# LED_Bar.net
KiCad netlist of a schematic drawn in EAGLE
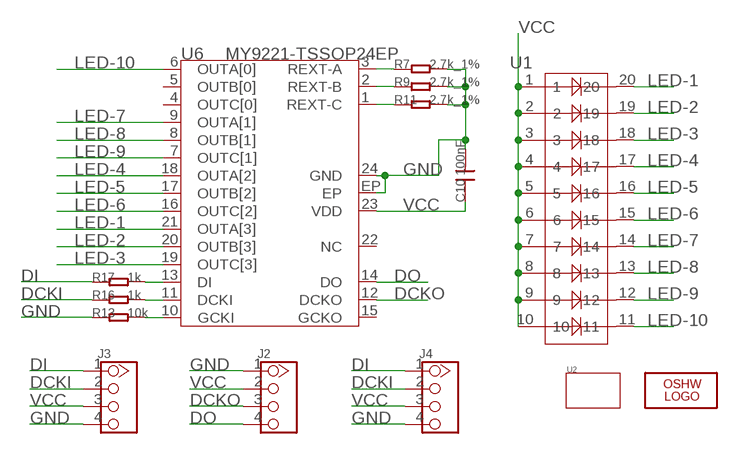
[diagram p0: schematic, sheet 1]

(export (version "E")
  (design (tool "Eeschema 10.0.6"))
  (components
    (comp (ref "C10")
      (value "100nF")
      (footprint "eagle-import:0603")
      (libsource (lib "eagle-import") (part "C-0603"))
    )
    (comp (ref "J2")
      (value "HEADER-4P-90D")
      (footprint "eagle-import:4P-2.54-90")
      (libsource (lib "eagle-import") (part "HEADER-4P-90D"))
    )
    (comp (ref "J3")
      (value "HEADER-4P'2.54-90D-FEMALE'")
      (footprint "eagle-import:4P-2.54-90D-FEMALE")
      (libsource (lib "eagle-import") (part "HEADER-4P'2.54-90D-FEMALE'"))
    )
    (comp (ref "J4")
      (value "TWIG-4P-2.0-2.0")
      (footprint "eagle-import:4P-2.0")
      (libsource (lib "eagle-import") (part "TWIG-4P-2.0-2.0"))
    )
    (comp (ref "LOGO1")
      (value "LOGO-OSHW-FILLX0150-NT")
      (footprint "eagle-import:OSHW_FILLX150_NOTEXT")
      (libsource (lib "eagle-import") (part "LOGO-OSHW-FILLX0150-NT"))
    )
    (comp (ref "R7")
      (value "2.7k_1%")
      (footprint "eagle-import:0603")
      (libsource (lib "eagle-import") (part "R-0603"))
    )
    (comp (ref "R9")
      (value "2.7k_1%")
      (footprint "eagle-import:0603")
      (libsource (lib "eagle-import") (part "R-0603"))
    )
    (comp (ref "R11")
      (value "2.7k_1%")
      (footprint "eagle-import:0603")
      (libsource (lib "eagle-import") (part "R-0603"))
    )
    (comp (ref "R13")
      (value "10k")
      (footprint "eagle-import:0603")
      (libsource (lib "eagle-import") (part "R-0603"))
    )
    (comp (ref "R16")
      (value "1k")
      (footprint "eagle-import:0603")
      (libsource (lib "eagle-import") (part "R-0603"))
    )
    (comp (ref "R17")
      (value "1k")
      (footprint "eagle-import:0603")
      (libsource (lib "eagle-import") (part "R-0603"))
    )
    (comp (ref "U1")
      (value "LED-20P")
      (footprint "eagle-import:20P-DIP-2.54-25.5X10.1X8.4H")
      (libsource (lib "eagle-import") (part "LED-20P"))
    )
    (comp (ref "U2")
      (value "TWIG-2U")
      (footprint "eagle-import:2U-DIM-W_-DRILL")
      (libsource (lib "eagle-import") (part "TWIG-2U"))
    )
    (comp (ref "U6")
      (value "MY9221-TSSOP24EP")
      (footprint "eagle-import:TSSOP24EP")
      (libsource (lib "eagle-import") (part "MY9221-TSSOP24EP"))
    )
  )
  (nets
    (net (code "1") (name "/DCKI") (class "Default")
      (node (ref "J3") (pin "2") (pinfunction "P$2_2") (pintype "bidirectional"))
      (node (ref "J4") (pin "2") (pinfunction "2_2") (pintype "bidirectional"))
      (node (ref "R16") (pin "1") (pinfunction "1_1") (pintype "passive"))
    )
    (net (code "2") (name "/DCKO") (class "Default")
      (node (ref "J2") (pin "3") (pinfunction "P$3_3") (pintype "bidirectional"))
      (node (ref "U6") (pin "12") (pinfunction "DCKO_12") (pintype "bidirectional"))
    )
    (net (code "3") (name "/DI") (class "Default")
      (node (ref "J3") (pin "1") (pinfunction "P$1_1") (pintype "bidirectional"))
      (node (ref "J4") (pin "1") (pinfunction "1_1") (pintype "bidirectional"))
      (node (ref "R17") (pin "1") (pinfunction "1_1") (pintype "passive"))
    )
    (net (code "4") (name "/DO") (class "Default")
      (node (ref "J2") (pin "4") (pinfunction "P$4_4") (pintype "bidirectional"))
      (node (ref "U6") (pin "14") (pinfunction "DO_14") (pintype "bidirectional"))
    )
    (net (code "5") (name "/GND") (class "Default")
      (node (ref "C10") (pin "2") (pinfunction "2_2") (pintype "passive"))
      (node (ref "J2") (pin "1") (pinfunction "P$1_1") (pintype "bidirectional"))
      (node (ref "J3") (pin "4") (pinfunction "P$4_4") (pintype "bidirectional"))
      (node (ref "J4") (pin "4") (pinfunction "4_4") (pintype "bidirectional"))
      (node (ref "R11") (pin "2") (pinfunction "2_2") (pintype "passive"))
      (node (ref "R13") (pin "1") (pinfunction "1_1") (pintype "passive"))
      (node (ref "R7") (pin "2") (pinfunction "2_2") (pintype "passive"))
      (node (ref "R9") (pin "2") (pinfunction "2_2") (pintype "passive"))
      (node (ref "U6") (pin "24") (pinfunction "GND_24") (pintype "power_in"))
      (node (ref "U6") (pin "EP") (pinfunction "EP_EP") (pintype "bidirectional"))
    )
    (net (code "6") (name "/LED-1") (class "Default")
      (node (ref "U1") (pin "20") (pinfunction "20_20") (pintype "bidirectional"))
      (node (ref "U6") (pin "21") (pinfunction "OUTA[3]_21") (pintype "bidirectional"))
    )
    (net (code "7") (name "/LED-2") (class "Default")
      (node (ref "U1") (pin "19") (pinfunction "19_19") (pintype "bidirectional"))
      (node (ref "U6") (pin "20") (pinfunction "OUTB[3]_20") (pintype "bidirectional"))
    )
    (net (code "8") (name "/LED-3") (class "Default")
      (node (ref "U1") (pin "18") (pinfunction "18_18") (pintype "bidirectional"))
      (node (ref "U6") (pin "19") (pinfunction "OUTC[3]_19") (pintype "bidirectional"))
    )
    (net (code "9") (name "/LED-4") (class "Default")
      (node (ref "U1") (pin "17") (pinfunction "17_17") (pintype "bidirectional"))
      (node (ref "U6") (pin "18") (pinfunction "OUTA[2]_18") (pintype "bidirectional"))
    )
    (net (code "10") (name "/LED-5") (class "Default")
      (node (ref "U1") (pin "16") (pinfunction "16_16") (pintype "bidirectional"))
      (node (ref "U6") (pin "17") (pinfunction "OUTB[2]_17") (pintype "bidirectional"))
    )
    (net (code "11") (name "/LED-6") (class "Default")
      (node (ref "U1") (pin "15") (pinfunction "15_15") (pintype "bidirectional"))
      (node (ref "U6") (pin "16") (pinfunction "OUTC[2]_16") (pintype "bidirectional"))
    )
    (net (code "12") (name "/LED-7") (class "Default")
      (node (ref "U1") (pin "14") (pinfunction "14_14") (pintype "bidirectional"))
      (node (ref "U6") (pin "9") (pinfunction "OUTA[1]_9") (pintype "bidirectional"))
    )
    (net (code "13") (name "/LED-8") (class "Default")
      (node (ref "U1") (pin "13") (pinfunction "13_13") (pintype "bidirectional"))
      (node (ref "U6") (pin "8") (pinfunction "OUTB[1]_8") (pintype "bidirectional"))
    )
    (net (code "14") (name "/LED-9") (class "Default")
      (node (ref "U1") (pin "12") (pinfunction "12_12") (pintype "bidirectional"))
      (node (ref "U6") (pin "7") (pinfunction "OUTC[1]_7") (pintype "bidirectional"))
    )
    (net (code "15") (name "/LED-10") (class "Default")
      (node (ref "U1") (pin "11") (pinfunction "11_11") (pintype "bidirectional"))
      (node (ref "U6") (pin "6") (pinfunction "OUTA[0]_6") (pintype "bidirectional"))
    )
    (net (code "16") (name "/VCC") (class "Default")
      (node (ref "C10") (pin "1") (pinfunction "1_1") (pintype "passive"))
      (node (ref "J2") (pin "2") (pinfunction "P$2_2") (pintype "bidirectional"))
      (node (ref "J3") (pin "3") (pinfunction "P$3_3") (pintype "bidirectional"))
      (node (ref "J4") (pin "3") (pinfunction "3_3") (pintype "bidirectional"))
      (node (ref "U1") (pin "1") (pinfunction "1_1") (pintype "bidirectional"))
      (node (ref "U1") (pin "10") (pinfunction "10_10") (pintype "bidirectional"))
      (node (ref "U1") (pin "2") (pinfunction "2_2") (pintype "bidirectional"))
      (node (ref "U1") (pin "3") (pinfunction "3_3") (pintype "bidirectional"))
      (node (ref "U1") (pin "4") (pinfunction "4_4") (pintype "bidirectional"))
      (node (ref "U1") (pin "5") (pinfunction "5_5") (pintype "bidirectional"))
      (node (ref "U1") (pin "6") (pinfunction "6_6") (pintype "bidirectional"))
      (node (ref "U1") (pin "7") (pinfunction "7_7") (pintype "bidirectional"))
      (node (ref "U1") (pin "8") (pinfunction "8_8") (pintype "bidirectional"))
      (node (ref "U1") (pin "9") (pinfunction "9_9") (pintype "bidirectional"))
      (node (ref "U6") (pin "23") (pinfunction "VDD_23") (pintype "power_in"))
    )
    (net (code "17") (name "Net-(U6-DCKI)") (class "Default")
      (node (ref "R16") (pin "2") (pinfunction "2_2") (pintype "passive"))
      (node (ref "U6") (pin "11") (pinfunction "DCKI_11") (pintype "bidirectional"))
    )
    (net (code "18") (name "Net-(U6-DI)") (class "Default")
      (node (ref "R17") (pin "2") (pinfunction "2_2") (pintype "passive"))
      (node (ref "U6") (pin "13") (pinfunction "DI_13") (pintype "bidirectional"))
    )
    (net (code "19") (name "Net-(U6-GCKI)") (class "Default")
      (node (ref "R13") (pin "2") (pinfunction "2_2") (pintype "passive"))
      (node (ref "U6") (pin "10") (pinfunction "GCKI_10") (pintype "bidirectional"))
    )
    (net (code "20") (name "Net-(U6-REXT-A)") (class "Default")
      (node (ref "R7") (pin "1") (pinfunction "1_1") (pintype "passive"))
      (node (ref "U6") (pin "3") (pinfunction "REXT-A_3") (pintype "bidirectional"))
    )
    (net (code "21") (name "Net-(U6-REXT-B)") (class "Default")
      (node (ref "R9") (pin "1") (pinfunction "1_1") (pintype "passive"))
      (node (ref "U6") (pin "2") (pinfunction "REXT-B_2") (pintype "bidirectional"))
    )
    (net (code "22") (name "Net-(U6-REXT-C)") (class "Default")
      (node (ref "R11") (pin "1") (pinfunction "1_1") (pintype "passive"))
      (node (ref "U6") (pin "1") (pinfunction "REXT-C_1") (pintype "bidirectional"))
    )
    (net (code "23") (name "unconnected-(U6-GCKO-Pad15)") (class "Default")
      (node (ref "U6") (pin "15") (pinfunction "GCKO_15") (pintype "bidirectional"))
    )
    (net (code "24") (name "unconnected-(U6-NC-Pad22)") (class "Default")
      (node (ref "U6") (pin "22") (pinfunction "NC_22") (pintype "bidirectional"))
    )
    (net (code "25") (name "unconnected-(U6-OUTB[0]-Pad5)") (class "Default")
      (node (ref "U6") (pin "5") (pinfunction "OUTB[0]_5") (pintype "bidirectional"))
    )
    (net (code "26") (name "unconnected-(U6-OUTC[0]-Pad4)") (class "Default")
      (node (ref "U6") (pin "4") (pinfunction "OUTC[0]_4") (pintype "bidirectional"))
    )
  )
)
